# Connection_Socket.net
KiCad netlist of a schematic drawn in Altium Designer
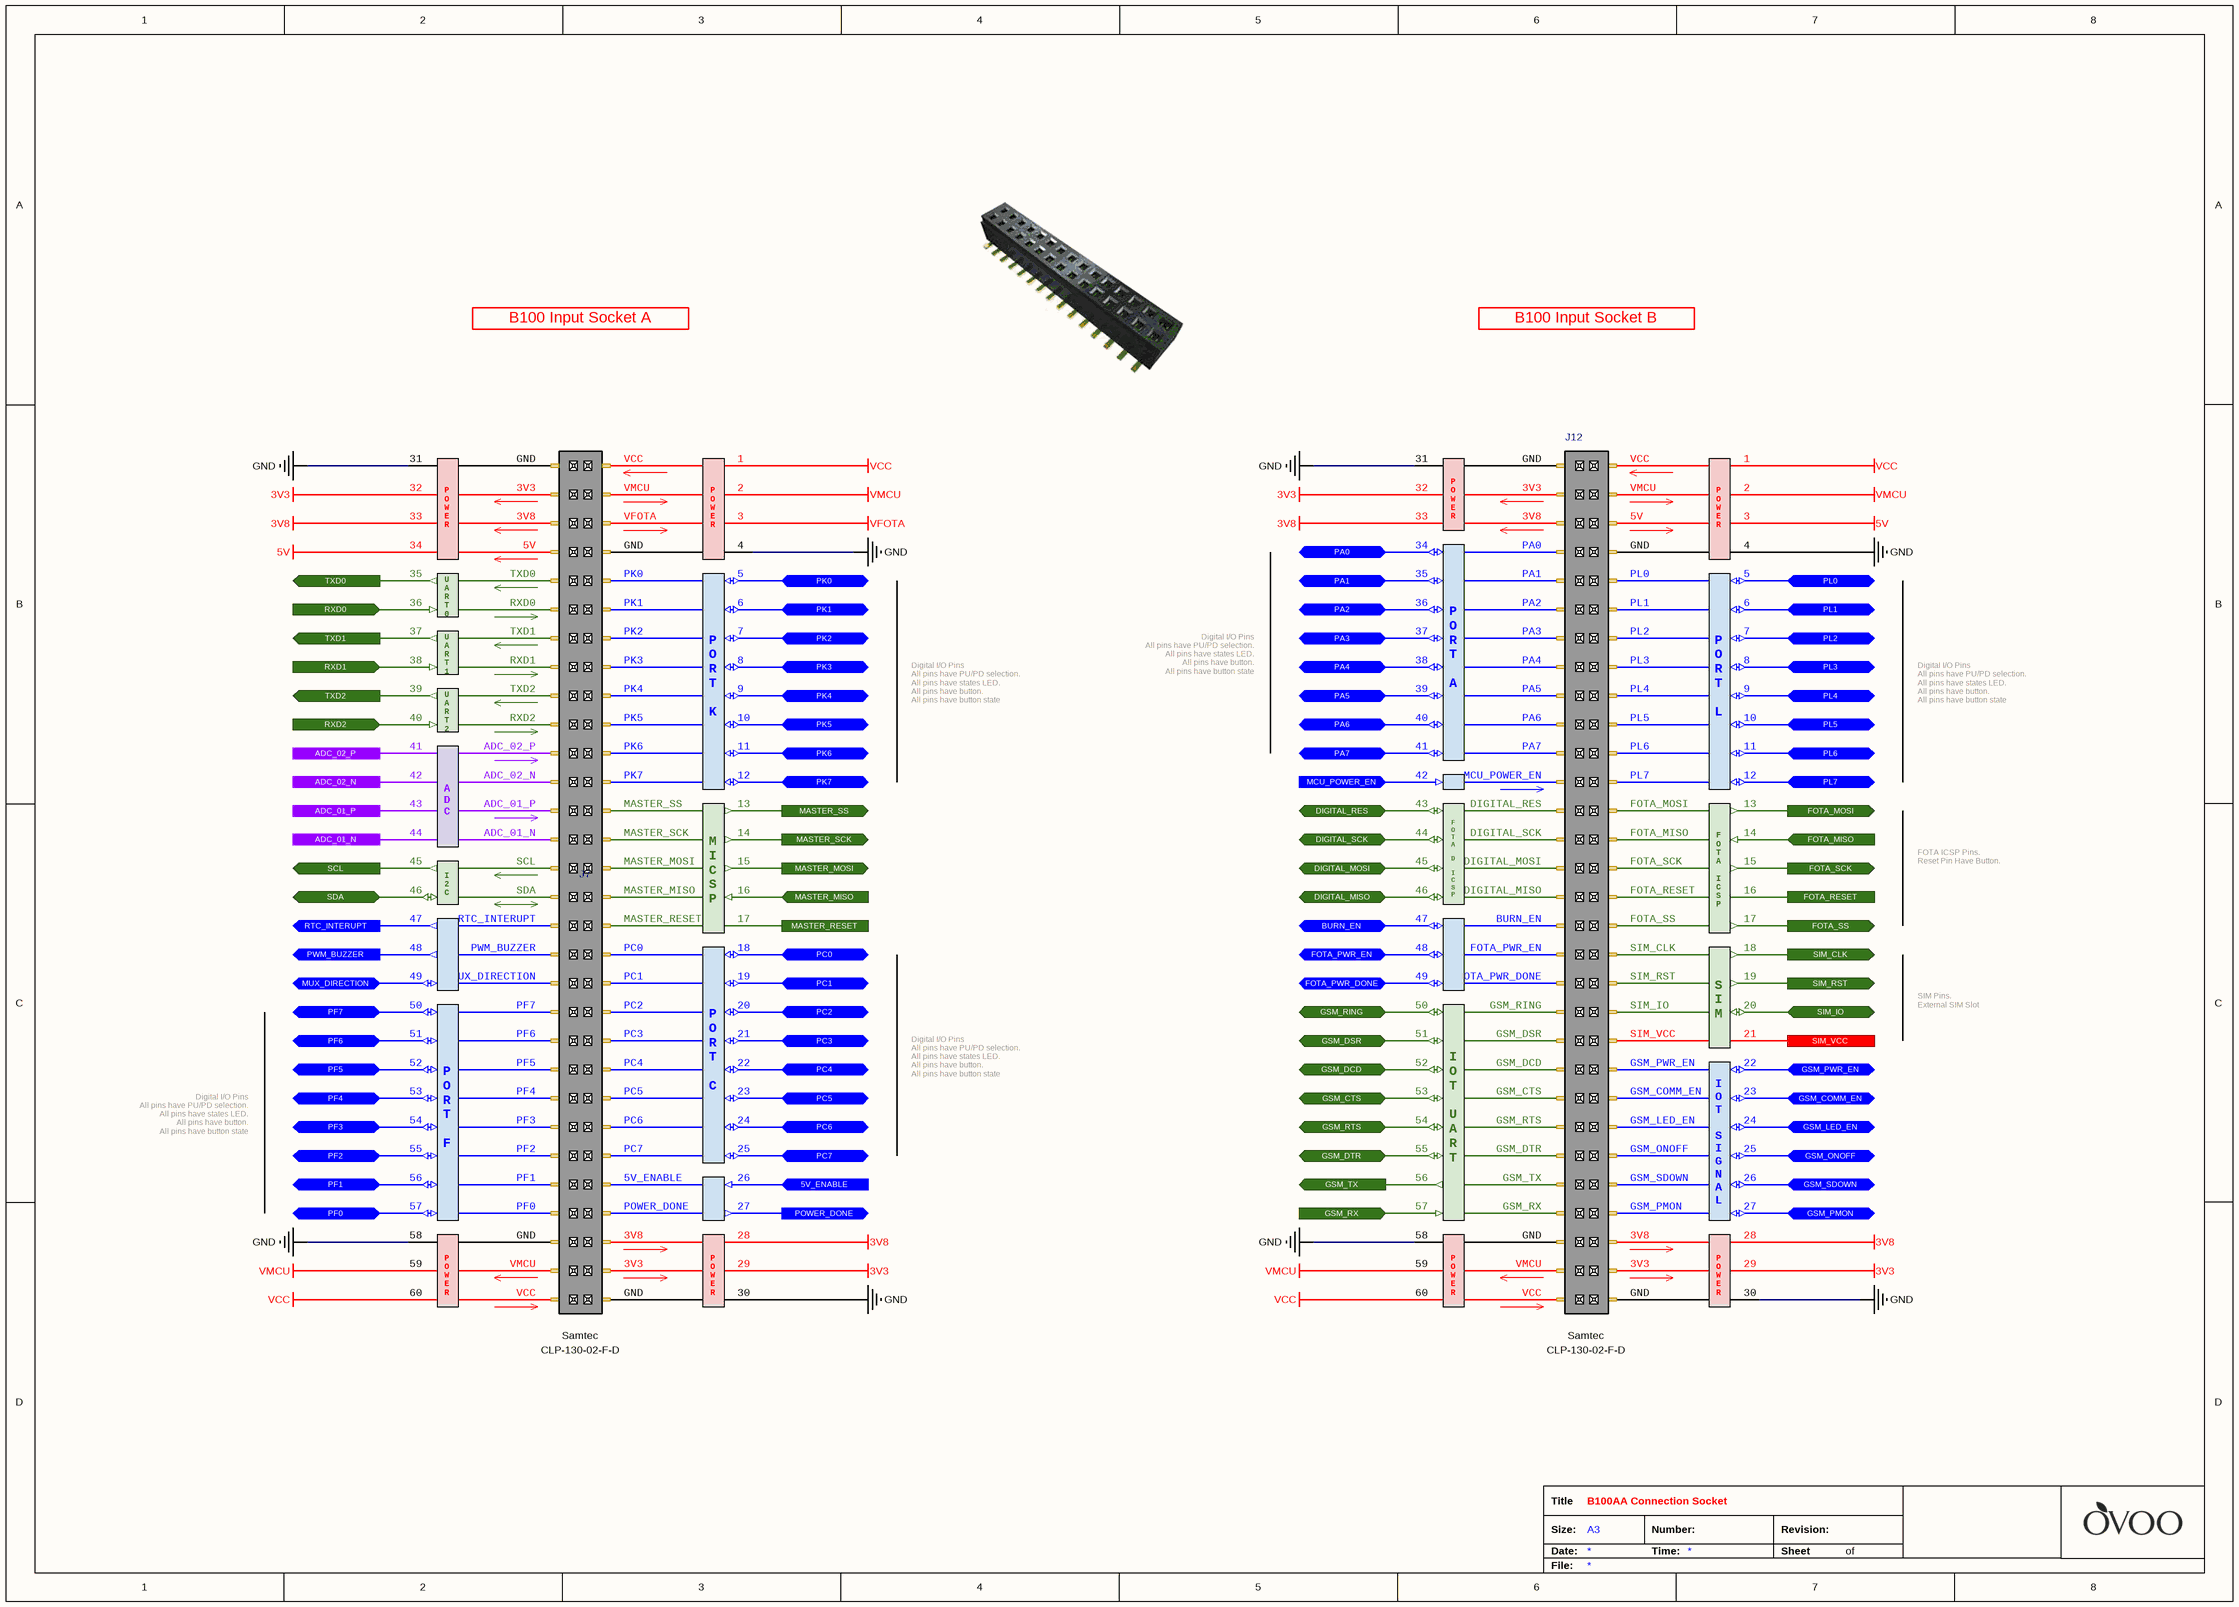
[diagram p0: Connection Socket.SchDoc]

(export (version "E")
  (design (tool "Eeschema 10.0.6"))
  (components
    (comp (ref "J7")
      (value "1.27 mm Pitch 2x30P Female Connector")
      (footprint "SAMTEC-CLP-130-02-X-D")
      (description "Headers & Wire Housings BREAKAWAY HDR VERT 60")
      (fields
        (field (name "MOUSER PART NUMBER") "200-CLP13002FD")
        (field (name "MANUFACTURER PART NUMBER") "CLP-130-02-F-D")
        (field (name "MANUFACTURER NAME") "Samtec")
      )
      (libsource (lib "Ovoo_Library") (part "Connector - B100 Female Socket [A]"))
    )
    (comp (ref "J12")
      (value "1.27 mm Pitch 2x30P Female Connector")
      (footprint "SAMTEC-CLP-130-02-X-D")
      (description "Headers & Wire Housings BREAKAWAY HDR VERT 60")
      (fields
        (field (name "MOUSER PART NUMBER") "200-CLP13002FD")
        (field (name "MANUFACTURER PART NUMBER") "CLP-130-02-F-D")
        (field (name "MANUFACTURER NAME") "Samtec")
      )
      (libsource (lib "Ovoo_Library") (part "Connector - B100 Female Socket [B]"))
    )
  )
  (nets
    (net (code "1") (name "/5V_ENABLE") (class "Default")
      (node (ref "J7") (pin "26") (pinfunction "Pin-26_26") (pintype "input"))
    )
    (net (code "2") (name "/ADC_01_N") (class "Default")
      (node (ref "J7") (pin "44") (pinfunction "Pin-44_44") (pintype "passive"))
    )
    (net (code "3") (name "/ADC_01_P") (class "Default")
      (node (ref "J7") (pin "43") (pinfunction "Pin-43_43") (pintype "passive"))
    )
    (net (code "4") (name "/ADC_02_N") (class "Default")
      (node (ref "J7") (pin "42") (pinfunction "Pin-42_42") (pintype "passive"))
    )
    (net (code "5") (name "/ADC_02_P") (class "Default")
      (node (ref "J7") (pin "41") (pinfunction "Pin-41_41") (pintype "passive"))
    )
    (net (code "6") (name "/BURN_EN") (class "Default")
      (node (ref "J12") (pin "47") (pinfunction "Pin-47_47") (pintype "bidirectional"))
    )
    (net (code "7") (name "/DIGITAL_MISO") (class "Default")
      (node (ref "J12") (pin "46") (pinfunction "Pin-46_46") (pintype "bidirectional"))
    )
    (net (code "8") (name "/DIGITAL_MOSI") (class "Default")
      (node (ref "J12") (pin "45") (pinfunction "Pin-45_45") (pintype "bidirectional"))
    )
    (net (code "9") (name "/DIGITAL_RES") (class "Default")
      (node (ref "J12") (pin "43") (pinfunction "Pin-43_43") (pintype "bidirectional"))
    )
    (net (code "10") (name "/DIGITAL_SCK") (class "Default")
      (node (ref "J12") (pin "44") (pinfunction "Pin-44_44") (pintype "bidirectional"))
    )
    (net (code "11") (name "/FOTA_MISO") (class "Default")
      (node (ref "J12") (pin "14") (pinfunction "Pin-14_14") (pintype "input"))
    )
    (net (code "12") (name "/FOTA_MOSI") (class "Default")
      (node (ref "J12") (pin "13") (pinfunction "Pin-13_13") (pintype "output"))
    )
    (net (code "13") (name "/FOTA_PWR_DONE") (class "Default")
      (node (ref "J12") (pin "49") (pinfunction "Pin-49_49") (pintype "bidirectional"))
    )
    (net (code "14") (name "/FOTA_PWR_EN") (class "Default")
      (node (ref "J12") (pin "48") (pinfunction "Pin-48_48") (pintype "bidirectional"))
    )
    (net (code "15") (name "/FOTA_RESET") (class "Default")
      (node (ref "J12") (pin "16") (pinfunction "Pin-16_16") (pintype "passive"))
    )
    (net (code "16") (name "/FOTA_SCK") (class "Default")
      (node (ref "J12") (pin "15") (pinfunction "Pin-15_15") (pintype "output"))
    )
    (net (code "17") (name "/FOTA_SS") (class "Default")
      (node (ref "J12") (pin "17") (pinfunction "Pin-17_17") (pintype "output"))
    )
    (net (code "18") (name "/GSM_COMM_EN") (class "Default")
      (node (ref "J12") (pin "23") (pinfunction "Pin-23_23") (pintype "bidirectional"))
    )
    (net (code "19") (name "/GSM_CTS") (class "Default")
      (node (ref "J12") (pin "53") (pinfunction "Pin-53_53") (pintype "bidirectional"))
    )
    (net (code "20") (name "/GSM_DCD") (class "Default")
      (node (ref "J12") (pin "52") (pinfunction "Pin-52_52") (pintype "bidirectional"))
    )
    (net (code "21") (name "/GSM_DSR") (class "Default")
      (node (ref "J12") (pin "51") (pinfunction "Pin-51_51") (pintype "bidirectional"))
    )
    (net (code "22") (name "/GSM_DTR") (class "Default")
      (node (ref "J12") (pin "55") (pinfunction "Pin-55_55") (pintype "bidirectional"))
    )
    (net (code "23") (name "/GSM_LED_EN") (class "Default")
      (node (ref "J12") (pin "24") (pinfunction "Pin-24_24") (pintype "bidirectional"))
    )
    (net (code "24") (name "/GSM_ONOFF") (class "Default")
      (node (ref "J12") (pin "25") (pinfunction "Pin-25_25") (pintype "bidirectional"))
    )
    (net (code "25") (name "/GSM_PMON") (class "Default")
      (node (ref "J12") (pin "27") (pinfunction "Pin-27_27") (pintype "bidirectional"))
    )
    (net (code "26") (name "/GSM_PWR_EN") (class "Default")
      (node (ref "J12") (pin "22") (pinfunction "Pin-22_22") (pintype "bidirectional"))
    )
    (net (code "27") (name "/GSM_RING") (class "Default")
      (node (ref "J12") (pin "50") (pinfunction "Pin-50_50") (pintype "bidirectional"))
    )
    (net (code "28") (name "/GSM_RTS") (class "Default")
      (node (ref "J12") (pin "54") (pinfunction "Pin-54_54") (pintype "bidirectional"))
    )
    (net (code "29") (name "/GSM_RX") (class "Default")
      (node (ref "J12") (pin "57") (pinfunction "Pin-57_57") (pintype "input"))
    )
    (net (code "30") (name "/GSM_SDOWN") (class "Default")
      (node (ref "J12") (pin "26") (pinfunction "Pin-26_26") (pintype "bidirectional"))
    )
    (net (code "31") (name "/GSM_TX") (class "Default")
      (node (ref "J12") (pin "56") (pinfunction "Pin-56_56") (pintype "output"))
    )
    (net (code "32") (name "/MASTER_MISO") (class "Default")
      (node (ref "J7") (pin "16") (pinfunction "Pin-16_16") (pintype "input"))
    )
    (net (code "33") (name "/MASTER_MOSI") (class "Default")
      (node (ref "J7") (pin "15") (pinfunction "Pin-15_15") (pintype "output"))
    )
    (net (code "34") (name "/MASTER_RESET") (class "Default")
      (node (ref "J7") (pin "17") (pinfunction "Pin-17_17") (pintype "passive"))
    )
    (net (code "35") (name "/MASTER_SCK") (class "Default")
      (node (ref "J7") (pin "14") (pinfunction "Pin-14_14") (pintype "output"))
    )
    (net (code "36") (name "/MASTER_SS") (class "Default")
      (node (ref "J7") (pin "13") (pinfunction "Pin-13_13") (pintype "output"))
    )
    (net (code "37") (name "/MCU_POWER_EN") (class "Default")
      (node (ref "J12") (pin "42") (pinfunction "Pin-42_42") (pintype "input"))
    )
    (net (code "38") (name "/MUX_DIRECTION") (class "Default")
      (node (ref "J7") (pin "49") (pinfunction "Pin-49_49") (pintype "bidirectional"))
    )
    (net (code "39") (name "/PA0") (class "Default")
      (node (ref "J12") (pin "34") (pinfunction "Pin-34_34") (pintype "bidirectional"))
    )
    (net (code "40") (name "/PA1") (class "Default")
      (node (ref "J12") (pin "35") (pinfunction "Pin-35_35") (pintype "bidirectional"))
    )
    (net (code "41") (name "/PA2") (class "Default")
      (node (ref "J12") (pin "36") (pinfunction "Pin-36_36") (pintype "bidirectional"))
    )
    (net (code "42") (name "/PA3") (class "Default")
      (node (ref "J12") (pin "37") (pinfunction "Pin-37_37") (pintype "bidirectional"))
    )
    (net (code "43") (name "/PA4") (class "Default")
      (node (ref "J12") (pin "38") (pinfunction "Pin-38_38") (pintype "bidirectional"))
    )
    (net (code "44") (name "/PA5") (class "Default")
      (node (ref "J12") (pin "39") (pinfunction "Pin-39_39") (pintype "bidirectional"))
    )
    (net (code "45") (name "/PA6") (class "Default")
      (node (ref "J12") (pin "40") (pinfunction "Pin-40_40") (pintype "bidirectional"))
    )
    (net (code "46") (name "/PA7") (class "Default")
      (node (ref "J12") (pin "41") (pinfunction "Pin-41_41") (pintype "bidirectional"))
    )
    (net (code "47") (name "/PC0") (class "Default")
      (node (ref "J7") (pin "18") (pinfunction "Pin-18_18") (pintype "bidirectional"))
    )
    (net (code "48") (name "/PC1") (class "Default")
      (node (ref "J7") (pin "19") (pinfunction "Pin-19_19") (pintype "bidirectional"))
    )
    (net (code "49") (name "/PC2") (class "Default")
      (node (ref "J7") (pin "20") (pinfunction "Pin-20_20") (pintype "bidirectional"))
    )
    (net (code "50") (name "/PC3") (class "Default")
      (node (ref "J7") (pin "21") (pinfunction "Pin-21_21") (pintype "bidirectional"))
    )
    (net (code "51") (name "/PC4") (class "Default")
      (node (ref "J7") (pin "22") (pinfunction "Pin-22_22") (pintype "bidirectional"))
    )
    (net (code "52") (name "/PC5") (class "Default")
      (node (ref "J7") (pin "23") (pinfunction "Pin-23_23") (pintype "bidirectional"))
    )
    (net (code "53") (name "/PC6") (class "Default")
      (node (ref "J7") (pin "24") (pinfunction "Pin-24_24") (pintype "bidirectional"))
    )
    (net (code "54") (name "/PC7") (class "Default")
      (node (ref "J7") (pin "25") (pinfunction "Pin-25_25") (pintype "bidirectional"))
    )
    (net (code "55") (name "/PF0") (class "Default")
      (node (ref "J7") (pin "57") (pinfunction "Pin-57_57") (pintype "bidirectional"))
    )
    (net (code "56") (name "/PF1") (class "Default")
      (node (ref "J7") (pin "56") (pinfunction "Pin-56_56") (pintype "bidirectional"))
    )
    (net (code "57") (name "/PF2") (class "Default")
      (node (ref "J7") (pin "55") (pinfunction "Pin-55_55") (pintype "bidirectional"))
    )
    (net (code "58") (name "/PF3") (class "Default")
      (node (ref "J7") (pin "54") (pinfunction "Pin-54_54") (pintype "bidirectional"))
    )
    (net (code "59") (name "/PF4") (class "Default")
      (node (ref "J7") (pin "53") (pinfunction "Pin-53_53") (pintype "bidirectional"))
    )
    (net (code "60") (name "/PF5") (class "Default")
      (node (ref "J7") (pin "52") (pinfunction "Pin-52_52") (pintype "bidirectional"))
    )
    (net (code "61") (name "/PF6") (class "Default")
      (node (ref "J7") (pin "51") (pinfunction "Pin-51_51") (pintype "bidirectional"))
    )
    (net (code "62") (name "/PF7") (class "Default")
      (node (ref "J7") (pin "50") (pinfunction "Pin-50_50") (pintype "bidirectional"))
    )
    (net (code "63") (name "/PK0") (class "Default")
      (node (ref "J7") (pin "5") (pinfunction "Pin-5_5") (pintype "bidirectional"))
    )
    (net (code "64") (name "/PK1") (class "Default")
      (node (ref "J7") (pin "6") (pinfunction "Pin-6_6") (pintype "bidirectional"))
    )
    (net (code "65") (name "/PK2") (class "Default")
      (node (ref "J7") (pin "7") (pinfunction "Pin-7_7") (pintype "bidirectional"))
    )
    (net (code "66") (name "/PK3") (class "Default")
      (node (ref "J7") (pin "8") (pinfunction "Pin-8_8") (pintype "bidirectional"))
    )
    (net (code "67") (name "/PK4") (class "Default")
      (node (ref "J7") (pin "9") (pinfunction "Pin-9_9") (pintype "bidirectional"))
    )
    (net (code "68") (name "/PK5") (class "Default")
      (node (ref "J7") (pin "10") (pinfunction "Pin-10_10") (pintype "bidirectional"))
    )
    (net (code "69") (name "/PK6") (class "Default")
      (node (ref "J7") (pin "11") (pinfunction "Pin-11_11") (pintype "bidirectional"))
    )
    (net (code "70") (name "/PK7") (class "Default")
      (node (ref "J7") (pin "12") (pinfunction "Pin-12_12") (pintype "bidirectional"))
    )
    (net (code "71") (name "/PL0") (class "Default")
      (node (ref "J12") (pin "5") (pinfunction "Pin-5_5") (pintype "bidirectional"))
    )
    (net (code "72") (name "/PL1") (class "Default")
      (node (ref "J12") (pin "6") (pinfunction "Pin-6_6") (pintype "bidirectional"))
    )
    (net (code "73") (name "/PL2") (class "Default")
      (node (ref "J12") (pin "7") (pinfunction "Pin-7_7") (pintype "bidirectional"))
    )
    (net (code "74") (name "/PL3") (class "Default")
      (node (ref "J12") (pin "8") (pinfunction "Pin-8_8") (pintype "bidirectional"))
    )
    (net (code "75") (name "/PL4") (class "Default")
      (node (ref "J12") (pin "9") (pinfunction "Pin-9_9") (pintype "bidirectional"))
    )
    (net (code "76") (name "/PL5") (class "Default")
      (node (ref "J12") (pin "10") (pinfunction "Pin-10_10") (pintype "bidirectional"))
    )
    (net (code "77") (name "/PL6") (class "Default")
      (node (ref "J12") (pin "11") (pinfunction "Pin-11_11") (pintype "bidirectional"))
    )
    (net (code "78") (name "/PL7") (class "Default")
      (node (ref "J12") (pin "12") (pinfunction "Pin-12_12") (pintype "bidirectional"))
    )
    (net (code "79") (name "/POWER_DONE") (class "Default")
      (node (ref "J7") (pin "27") (pinfunction "Pin-27_27") (pintype "output"))
    )
    (net (code "80") (name "/PWM_BUZZER") (class "Default")
      (node (ref "J7") (pin "48") (pinfunction "Pin-48_48") (pintype "output"))
    )
    (net (code "81") (name "/RTC_INTERUPT") (class "Default")
      (node (ref "J7") (pin "47") (pinfunction "Pin-47_47") (pintype "output"))
    )
    (net (code "82") (name "/RXD0") (class "Default")
      (node (ref "J7") (pin "36") (pinfunction "Pin-36_36") (pintype "input"))
    )
    (net (code "83") (name "/RXD1") (class "Default")
      (node (ref "J7") (pin "38") (pinfunction "Pin-38_38") (pintype "input"))
    )
    (net (code "84") (name "/RXD2") (class "Default")
      (node (ref "J7") (pin "40") (pinfunction "Pin-40_40") (pintype "input"))
    )
    (net (code "85") (name "/SCL") (class "Default")
      (node (ref "J7") (pin "45") (pinfunction "Pin-45_45") (pintype "output"))
    )
    (net (code "86") (name "/SDA") (class "Default")
      (node (ref "J7") (pin "46") (pinfunction "Pin-46_46") (pintype "bidirectional"))
    )
    (net (code "87") (name "/SIM_CLK") (class "Default")
      (node (ref "J12") (pin "18") (pinfunction "Pin-18_18") (pintype "output"))
    )
    (net (code "88") (name "/SIM_IO") (class "Default")
      (node (ref "J12") (pin "20") (pinfunction "Pin-20_20") (pintype "bidirectional"))
    )
    (net (code "89") (name "/SIM_RST") (class "Default")
      (node (ref "J12") (pin "19") (pinfunction "Pin-19_19") (pintype "output"))
    )
    (net (code "90") (name "/SIM_VCC") (class "Default")
      (node (ref "J12") (pin "21") (pinfunction "Pin-21_21") (pintype "power_in"))
    )
    (net (code "91") (name "/TXD0") (class "Default")
      (node (ref "J7") (pin "35") (pinfunction "Pin-35_35") (pintype "output"))
    )
    (net (code "92") (name "/TXD1") (class "Default")
      (node (ref "J7") (pin "37") (pinfunction "Pin-37_37") (pintype "output"))
    )
    (net (code "93") (name "/TXD2") (class "Default")
      (node (ref "J7") (pin "39") (pinfunction "Pin-39_39") (pintype "output"))
    )
    (net (code "94") (name "3V3") (class "Default")
      (node (ref "J12") (pin "29") (pinfunction "Pin-29_29") (pintype "power_in"))
      (node (ref "J12") (pin "32") (pinfunction "Pin-32_32") (pintype "power_in"))
      (node (ref "J7") (pin "29") (pinfunction "Pin-29_29") (pintype "passive"))
      (node (ref "J7") (pin "32") (pinfunction "Pin-32_32") (pintype "power_in"))
    )
    (net (code "95") (name "3V8") (class "Default")
      (node (ref "J12") (pin "28") (pinfunction "Pin-28_28") (pintype "power_in"))
      (node (ref "J12") (pin "33") (pinfunction "Pin-33_33") (pintype "power_in"))
      (node (ref "J7") (pin "28") (pinfunction "Pin-28_28") (pintype "passive"))
      (node (ref "J7") (pin "33") (pinfunction "Pin-33_33") (pintype "power_in"))
    )
    (net (code "96") (name "5V") (class "Default")
      (node (ref "J12") (pin "3") (pinfunction "Pin-3_3") (pintype "power_in"))
      (node (ref "J7") (pin "34") (pinfunction "Pin-34_34") (pintype "power_in"))
    )
    (net (code "97") (name "GND") (class "Default")
      (node (ref "J12") (pin "30") (pinfunction "Pin-30_30") (pintype "power_in"))
      (node (ref "J12") (pin "31") (pinfunction "Pin-31_31") (pintype "power_in"))
      (node (ref "J12") (pin "4") (pinfunction "Pin-4_4") (pintype "power_in"))
      (node (ref "J12") (pin "58") (pinfunction "Pin-58_58") (pintype "power_in"))
      (node (ref "J7") (pin "30") (pinfunction "Pin-30_30") (pintype "passive"))
      (node (ref "J7") (pin "31") (pinfunction "Pin-31_31") (pintype "power_in"))
      (node (ref "J7") (pin "4") (pinfunction "Pin-4_4") (pintype "power_in"))
      (node (ref "J7") (pin "58") (pinfunction "Pin-58_58") (pintype "power_in"))
    )
    (net (code "98") (name "VCC") (class "Default")
      (node (ref "J12") (pin "1") (pinfunction "Pin-1_1") (pintype "power_in"))
      (node (ref "J12") (pin "60") (pinfunction "Pin-60_60") (pintype "power_in"))
      (node (ref "J7") (pin "1") (pinfunction "Pin-1_1") (pintype "power_in"))
      (node (ref "J7") (pin "60") (pinfunction "Pin-60_60") (pintype "power_in"))
    )
    (net (code "99") (name "VFOTA") (class "Default")
      (node (ref "J7") (pin "3") (pinfunction "Pin-3_3") (pintype "power_in"))
    )
    (net (code "100") (name "VMCU") (class "Default")
      (node (ref "J12") (pin "2") (pinfunction "Pin-2_2") (pintype "power_in"))
      (node (ref "J12") (pin "59") (pinfunction "Pin-59_59") (pintype "power_in"))
      (node (ref "J7") (pin "2") (pinfunction "Pin-2_2") (pintype "power_in"))
      (node (ref "J7") (pin "59") (pinfunction "Pin-59_59") (pintype "power_in"))
    )
  )
)
